# SCH_03_Power.net
KiCad netlist of a schematic drawn in Altium Designer
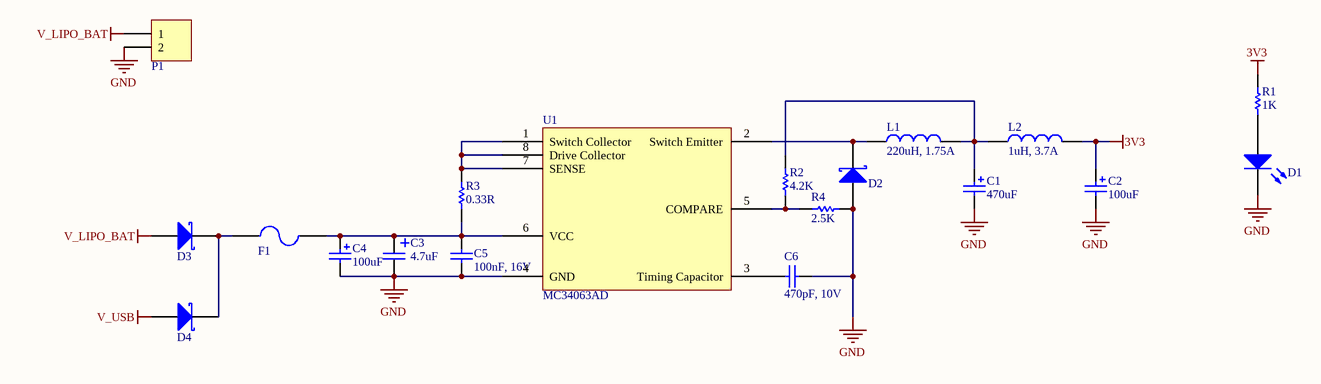
[diagram p0: SCH_03_Power.SchDoc]

(export (version "E")
  (design (tool "Eeschema 10.0.6"))
  (components
    (comp (ref "C1")
      (value "470uF")
      (footprint "CAP ALU SIZE G")
      (description "Polarized Capacitor (Radial)")
      (fields (field (name "Comment") "Cap Pol SMD"))
      (libsource (lib "PIF_Library") (part "Cap Pol SMD"))
    )
    (comp (ref "C2")
      (value "100uF")
      (footprint "CAP ALU SIZE D")
      (description "Polarized Capacitor (Radial)")
      (fields (field (name "Comment") "Cap Pol SMD"))
      (libsource (lib "PIF_Library") (part "Cap Pol SMD"))
    )
    (comp (ref "C3")
      (value "4.7uF")
      (footprint "CAPMP3216X18N")
      (fields (field (name "Comment") "Tantalum Capacitor"))
      (libsource (lib "MiclsLib") (part "Tantalum Capacitor"))
    )
    (comp (ref "C4")
      (value "100uF")
      (footprint "CAP ALU SIZE D")
      (description "Polarized Capacitor (Radial)")
      (fields (field (name "Comment") "Cap Pol SMD"))
      (libsource (lib "PIF_Library") (part "Cap Pol SMD"))
    )
    (comp (ref "C5")
      (value "100nF, 16V")
      (footprint "WCAP-CSGP_0805_H=0.8mm_Reflow")
      (description "WCAP-CSGP Multilayer Ceramic Chip Capacitor, General Purpose, size 0805, X7R, 100nF, 16V")
      (fields
        (field (name "MANUFACTURER PART NUMBER") "885012207045")
        (field (name "MANUFACTURER") "Wurth Elektronik")
      )
      (libsource (lib "Altium_WCAP-CSGP (rev20a)") (part "885012207045"))
    )
    (comp (ref "C6")
      (value "470pF, 10V")
      (footprint "WCAP-CSGP_0805_H=0.8mm_Reflow")
      (description "WCAP-CSGP Multilayer Ceramic Chip Capacitor, General Purpose, size 0805, X7R, 100nF, 10V")
      (fields
        (field (name "MANUFACTURER PART NUMBER") "885012207016")
        (field (name "MANUFACTURER") "Wurth Elektronik")
      )
      (libsource (lib "Altium_WCAP-CSGP (rev20a)") (part "885012207016"))
    )
    (comp (ref "D1")
      (value "LED SMD")
      (footprint "LED_0805_Blue")
      (description "LED")
      (libsource (lib "PIF_Library") (part "LED SMD"))
    )
    (comp (ref "D2")
      (value "D Schottky")
      (footprint "SS34")
      (description "Schottky Diode")
      (fields (field (name "PUBLISHER") "Altium Limited"))
      (libsource (lib "PIF_Library") (part "D Schottky"))
    )
    (comp (ref "D3")
      (value "D Schottky")
      (footprint "SS34")
      (description "Schottky Diode")
      (fields (field (name "PUBLISHER") "Altium Limited"))
      (libsource (lib "PIF_Library") (part "D Schottky"))
    )
    (comp (ref "D4")
      (value "D Schottky")
      (footprint "SS34")
      (description "Schottky Diode")
      (fields (field (name "PUBLISHER") "Altium Limited"))
      (libsource (lib "PIF_Library") (part "D Schottky"))
    )
    (comp (ref "F1") (value "Fuse") (footprint "FUSE SMD") (libsource (lib "PIF_Library") (part "Fuse")))
    (comp (ref "L1")
      (value "220uH, 1.75A")
      (footprint "WE-PD2A_5848")
      (description "WE-PD2A SMT Power Inductor, size 5848, 220uH, 0.41A")
      (fields
        (field (name "MANUFACTURER PART NUMBER") "784774222")
        (field (name "MANUFACTURER") "Wurth Elektronik")
      )
      (libsource (lib "Altium_WE-PD2A (rev20a)") (part "784774222"))
    )
    (comp (ref "L2")
      (value "1uH, 3.7A")
      (footprint "WE-PD2A_5848")
      (description "WE-PD2A SMT Power Inductor, size 5848, 0.33uH, 10.8A")
      (fields
        (field (name "MANUFACTURER PART NUMBER") "784774003")
        (field (name "MANUFACTURER") "Wurth Elektronik")
      )
      (libsource (lib "Altium_WE-PD2A (rev20a)") (part "784774003"))
    )
    (comp (ref "P1")
      (value "Domino 2")
      (footprint "DOMINO 2- 5mm")
      (description "Domino, 2-Pin")
      (fields (field (name "PUBLISHER") "Altium Limited"))
      (libsource (lib "PIF_Library") (part "Domino 2"))
    )
    (comp (ref "R1")
      (value "1K")
      (footprint "RES-SM-0603")
      (description "Resistor")
      (fields (field (name "Comment") "RESISTOR SMD"))
      (libsource (lib "PIF_Library") (part "RESISTOR SMD"))
    )
    (comp (ref "R2")
      (value "4.2K")
      (footprint "RES-SM-0805")
      (description "Resistor")
      (fields (field (name "Comment") "RESISTOR SMD"))
      (libsource (lib "PIF_Library") (part "RESISTOR SMD"))
    )
    (comp (ref "R3")
      (value "0.33R")
      (footprint "RES-SM-0805")
      (description "Resistor")
      (fields (field (name "Comment") "RESISTOR SMD"))
      (libsource (lib "PIF_Library") (part "RESISTOR SMD"))
    )
    (comp (ref "R4")
      (value "2.5K")
      (footprint "RES-SM-0805")
      (description "Resistor")
      (fields (field (name "Comment") "RESISTOR SMD"))
      (libsource (lib "PIF_Library") (part "RESISTOR SMD"))
    )
    (comp (ref "U1")
      (value "MC34063AD")
      (footprint "SOIC127P600X170-8N")
      (description "1.5-A boost, buck, inverting switching regulator, operation from 0°C to 70°C")
      (fields (field (name "MANUFACTURER") "Texas Instruments"))
      (libsource (lib "MiclsLib") (part "MC34063"))
    )
  )
  (nets
    (net (code "1") (name "3V3") (class "Default")
      (node (ref "C2") (pin "1") (pinfunction "1_1") (pintype "passive"))
      (node (ref "L2") (pin "2") (pinfunction "2_2") (pintype "passive"))
      (node (ref "R1") (pin "2") (pinfunction "2_2") (pintype "passive"))
    )
    (net (code "2") (name "GND") (class "Default")
      (node (ref "C1") (pin "2") (pinfunction "2_2") (pintype "passive"))
      (node (ref "C2") (pin "2") (pinfunction "2_2") (pintype "passive"))
      (node (ref "C3") (pin "2") (pinfunction "2_2") (pintype "passive"))
      (node (ref "C4") (pin "2") (pinfunction "2_2") (pintype "passive"))
      (node (ref "C5") (pin "1") (pinfunction "1_1") (pintype "passive"))
      (node (ref "C6") (pin "2") (pinfunction "2_2") (pintype "passive"))
      (node (ref "D1") (pin "2") (pinfunction "K_2") (pintype "passive"))
      (node (ref "D2") (pin "1") (pinfunction "A_1") (pintype "passive"))
      (node (ref "P1") (pin "2") (pinfunction "2_2") (pintype "passive"))
      (node (ref "R4") (pin "1") (pinfunction "1_1") (pintype "passive"))
      (node (ref "U1") (pin "4") (pinfunction "GND_4") (pintype "passive"))
    )
    (net (code "3") (name "Net-(C1-Pad1)") (class "Default")
      (node (ref "C1") (pin "1") (pinfunction "1_1") (pintype "passive"))
      (node (ref "L1") (pin "2") (pinfunction "2_2") (pintype "passive"))
      (node (ref "L2") (pin "1") (pinfunction "1_1") (pintype "passive"))
      (node (ref "R2") (pin "2") (pinfunction "2_2") (pintype "passive"))
    )
    (net (code "4") (name "Net-(D1-A)") (class "Default")
      (node (ref "D1") (pin "1") (pinfunction "A_1") (pintype "passive"))
      (node (ref "R1") (pin "1") (pinfunction "1_1") (pintype "passive"))
    )
    (net (code "5") (name "Net-(D2-K)") (class "Default")
      (node (ref "D2") (pin "2") (pinfunction "K_2") (pintype "passive"))
      (node (ref "L1") (pin "1") (pinfunction "1_1") (pintype "passive"))
      (node (ref "U1") (pin "2") (pinfunction "Switch_Emitter_2") (pintype "passive"))
    )
    (net (code "6") (name "Net-(D3-K)") (class "Default")
      (node (ref "D3") (pin "2") (pinfunction "K_2") (pintype "passive"))
      (node (ref "D4") (pin "2") (pinfunction "K_2") (pintype "passive"))
      (node (ref "F1") (pin "1") (pinfunction "1_1") (pintype "passive"))
    )
    (net (code "7") (name "Net-(U1-COMPARE)") (class "Default")
      (node (ref "R2") (pin "1") (pinfunction "1_1") (pintype "passive"))
      (node (ref "R4") (pin "2") (pinfunction "2_2") (pintype "passive"))
      (node (ref "U1") (pin "5") (pinfunction "COMPARE_5") (pintype "passive"))
    )
    (net (code "8") (name "Net-(U1-Drive_Collector)") (class "Default")
      (node (ref "R3") (pin "2") (pinfunction "2_2") (pintype "passive"))
      (node (ref "U1") (pin "1") (pinfunction "Switch_Collector_1") (pintype "passive"))
      (node (ref "U1") (pin "7") (pinfunction "SENSE_7") (pintype "passive"))
      (node (ref "U1") (pin "8") (pinfunction "Drive_Collector_8") (pintype "passive"))
    )
    (net (code "9") (name "Net-(U1-Timing_Capacitor)") (class "Default")
      (node (ref "C6") (pin "1") (pinfunction "1_1") (pintype "passive"))
      (node (ref "U1") (pin "3") (pinfunction "Timing_Capacitor_3") (pintype "passive"))
    )
    (net (code "10") (name "Net-(U1-VCC)") (class "Default")
      (node (ref "C3") (pin "1") (pinfunction "1_1") (pintype "passive"))
      (node (ref "C4") (pin "1") (pinfunction "1_1") (pintype "passive"))
      (node (ref "C5") (pin "2") (pinfunction "2_2") (pintype "passive"))
      (node (ref "F1") (pin "2") (pinfunction "2_2") (pintype "passive"))
      (node (ref "R3") (pin "1") (pinfunction "1_1") (pintype "passive"))
      (node (ref "U1") (pin "6") (pinfunction "VCC_6") (pintype "passive"))
    )
    (net (code "11") (name "V_LIPO_BAT") (class "Default")
      (node (ref "D3") (pin "1") (pinfunction "A_1") (pintype "passive"))
      (node (ref "P1") (pin "1") (pinfunction "1_1") (pintype "passive"))
    )
    (net (code "12") (name "V_USB") (class "Default")
      (node (ref "D4") (pin "1") (pinfunction "A_1") (pintype "passive"))
    )
  )
)
